# mcp23017.net
KiCad netlist of a schematic drawn in EAGLE
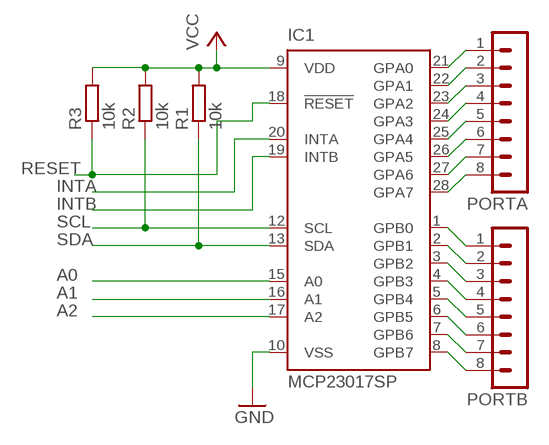
[diagram p0: schematic, sheet 1]

(export (version "E")
  (design (tool "Eeschema 10.0.6"))
  (components
    (comp (ref "IC1")
      (value "MCP23017SP")
      (footprint "eagle-import:DIL28-3")
      (fields (field (name "MF") "MICROCHIP") (field (name "MPN") "MCP23017-E/SP"))
      (libsource (lib "eagle-import") (part "MCP23017SP"))
    )
    (comp (ref "PORTA")
      (value "MA08-1")
      (footprint "eagle-import:MA08-1")
      (libsource (lib "eagle-import") (part "MA08-1"))
    )
    (comp (ref "PORTB")
      (value "MA08-1")
      (footprint "eagle-import:MA08-1")
      (libsource (lib "eagle-import") (part "MA08-1"))
    )
    (comp (ref "R1")
      (value "10k")
      (footprint "eagle-import:0207_7")
      (libsource (lib "eagle-import") (part "R-EU_0207/7"))
    )
    (comp (ref "R2")
      (value "10k")
      (footprint "eagle-import:0207_7")
      (libsource (lib "eagle-import") (part "R-EU_0207/7"))
    )
    (comp (ref "R3")
      (value "10k")
      (footprint "eagle-import:0207_7")
      (libsource (lib "eagle-import") (part "R-EU_0207/7"))
    )
  )
  (nets
    (net (code "1") (name "/A0") (class "Default")
      (node (ref "IC1") (pin "15") (pinfunction "A0_15") (pintype "input"))
    )
    (net (code "2") (name "/A1") (class "Default")
      (node (ref "IC1") (pin "16") (pinfunction "A1_16") (pintype "input"))
    )
    (net (code "3") (name "/A2") (class "Default")
      (node (ref "IC1") (pin "17") (pinfunction "A2_17") (pintype "input"))
    )
    (net (code "4") (name "/INTA") (class "Default")
      (node (ref "IC1") (pin "20") (pinfunction "INTA_20") (pintype "output"))
    )
    (net (code "5") (name "/INTB") (class "Default")
      (node (ref "IC1") (pin "19") (pinfunction "INTB_19") (pintype "output"))
    )
    (net (code "6") (name "/RESET") (class "Default")
      (node (ref "IC1") (pin "18") (pinfunction "~{RESET}_18") (pintype "input"))
      (node (ref "R3") (pin "1") (pinfunction "1_1") (pintype "passive"))
    )
    (net (code "7") (name "/SCL") (class "Default")
      (node (ref "IC1") (pin "12") (pinfunction "SCL_12") (pintype "input"))
      (node (ref "R2") (pin "1") (pinfunction "1_1") (pintype "passive"))
    )
    (net (code "8") (name "/SDA") (class "Default")
      (node (ref "IC1") (pin "13") (pinfunction "SDA_13") (pintype "bidirectional"))
      (node (ref "R1") (pin "1") (pinfunction "1_1") (pintype "passive"))
    )
    (net (code "9") (name "GND") (class "Default")
      (node (ref "IC1") (pin "10") (pinfunction "VSS_10") (pintype "power_in"))
    )
    (net (code "10") (name "Net-(IC1-GPA0)") (class "Default")
      (node (ref "IC1") (pin "21") (pinfunction "GPA0_21") (pintype "bidirectional"))
      (node (ref "PORTA") (pin "1") (pinfunction "1_1") (pintype "passive"))
    )
    (net (code "11") (name "Net-(IC1-GPA1)") (class "Default")
      (node (ref "IC1") (pin "22") (pinfunction "GPA1_22") (pintype "bidirectional"))
      (node (ref "PORTA") (pin "2") (pinfunction "2_2") (pintype "passive"))
    )
    (net (code "12") (name "Net-(IC1-GPA2)") (class "Default")
      (node (ref "IC1") (pin "23") (pinfunction "GPA2_23") (pintype "bidirectional"))
      (node (ref "PORTA") (pin "3") (pinfunction "3_3") (pintype "passive"))
    )
    (net (code "13") (name "Net-(IC1-GPA3)") (class "Default")
      (node (ref "IC1") (pin "24") (pinfunction "GPA3_24") (pintype "bidirectional"))
      (node (ref "PORTA") (pin "4") (pinfunction "4_4") (pintype "passive"))
    )
    (net (code "14") (name "Net-(IC1-GPA4)") (class "Default")
      (node (ref "IC1") (pin "25") (pinfunction "GPA4_25") (pintype "bidirectional"))
      (node (ref "PORTA") (pin "5") (pinfunction "5_5") (pintype "passive"))
    )
    (net (code "15") (name "Net-(IC1-GPA5)") (class "Default")
      (node (ref "IC1") (pin "26") (pinfunction "GPA5_26") (pintype "bidirectional"))
      (node (ref "PORTA") (pin "6") (pinfunction "6_6") (pintype "passive"))
    )
    (net (code "16") (name "Net-(IC1-GPA6)") (class "Default")
      (node (ref "IC1") (pin "27") (pinfunction "GPA6_27") (pintype "bidirectional"))
      (node (ref "PORTA") (pin "7") (pinfunction "7_7") (pintype "passive"))
    )
    (net (code "17") (name "Net-(IC1-GPA7)") (class "Default")
      (node (ref "IC1") (pin "28") (pinfunction "GPA7_28") (pintype "bidirectional"))
      (node (ref "PORTA") (pin "8") (pinfunction "8_8") (pintype "passive"))
    )
    (net (code "18") (name "Net-(IC1-GPB0)") (class "Default")
      (node (ref "IC1") (pin "1") (pinfunction "GPB0_1") (pintype "bidirectional"))
      (node (ref "PORTB") (pin "1") (pinfunction "1_1") (pintype "passive"))
    )
    (net (code "19") (name "Net-(IC1-GPB1)") (class "Default")
      (node (ref "IC1") (pin "2") (pinfunction "GPB1_2") (pintype "bidirectional"))
      (node (ref "PORTB") (pin "2") (pinfunction "2_2") (pintype "passive"))
    )
    (net (code "20") (name "Net-(IC1-GPB2)") (class "Default")
      (node (ref "IC1") (pin "3") (pinfunction "GPB2_3") (pintype "bidirectional"))
      (node (ref "PORTB") (pin "3") (pinfunction "3_3") (pintype "passive"))
    )
    (net (code "21") (name "Net-(IC1-GPB3)") (class "Default")
      (node (ref "IC1") (pin "4") (pinfunction "GPB3_4") (pintype "bidirectional"))
      (node (ref "PORTB") (pin "4") (pinfunction "4_4") (pintype "passive"))
    )
    (net (code "22") (name "Net-(IC1-GPB4)") (class "Default")
      (node (ref "IC1") (pin "5") (pinfunction "GPB4_5") (pintype "bidirectional"))
      (node (ref "PORTB") (pin "5") (pinfunction "5_5") (pintype "passive"))
    )
    (net (code "23") (name "Net-(IC1-GPB5)") (class "Default")
      (node (ref "IC1") (pin "6") (pinfunction "GPB5_6") (pintype "bidirectional"))
      (node (ref "PORTB") (pin "6") (pinfunction "6_6") (pintype "passive"))
    )
    (net (code "24") (name "Net-(IC1-GPB6)") (class "Default")
      (node (ref "IC1") (pin "7") (pinfunction "GPB6_7") (pintype "bidirectional"))
      (node (ref "PORTB") (pin "7") (pinfunction "7_7") (pintype "passive"))
    )
    (net (code "25") (name "Net-(IC1-GPB7)") (class "Default")
      (node (ref "IC1") (pin "8") (pinfunction "GPB7_8") (pintype "bidirectional"))
      (node (ref "PORTB") (pin "8") (pinfunction "8_8") (pintype "passive"))
    )
    (net (code "26") (name "VCC") (class "Default")
      (node (ref "IC1") (pin "9") (pinfunction "VDD_9") (pintype "power_in"))
      (node (ref "R1") (pin "2") (pinfunction "2_2") (pintype "passive"))
      (node (ref "R2") (pin "2") (pinfunction "2_2") (pintype "passive"))
      (node (ref "R3") (pin "2") (pinfunction "2_2") (pintype "passive"))
    )
  )
)
